# YOTSUBA__Y_Z_ver_1_1b.net
KiCad netlist of a schematic drawn in EAGLE
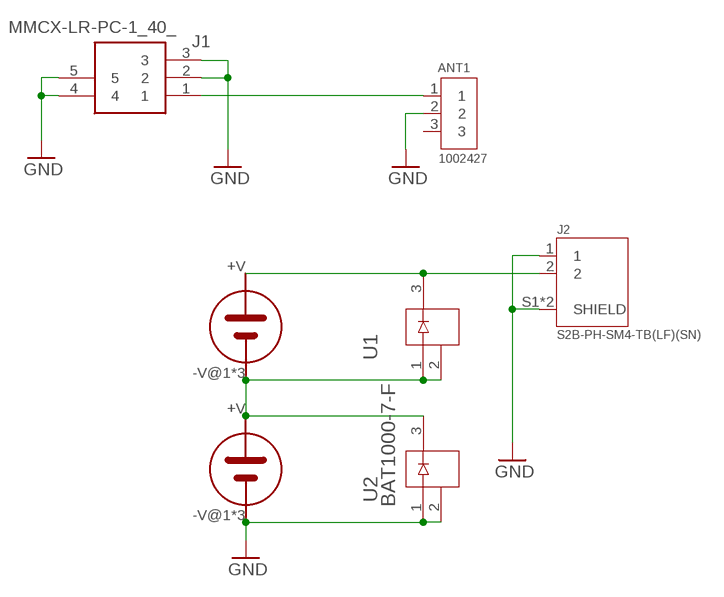
[diagram p0: schematic, sheet 1]

(export (version "E")
  (design (tool "Eeschema 10.0.6"))
  (components
    (comp (ref "ANT1")
      (value "1002427")
      (footprint "eagle-import:ANTENNA_1002427")
      (fields (field (name "DIGI-KEY_PART_NUMBER") "478-1002427TR-ND") (field (name "MF") "Ethertronics/AVX"))
      (libsource (lib "eagle-import") (part "1002427"))
    )
    (comp (ref "J1")
      (value "MMCX-LR-PC-1_40_")
      (footprint "eagle-import:MMCXLRPC140")
      (fields
        (field (name "MANUFACTURER_PART_NUMBER") "MMCX-LR-PC-1(40)")
        (field (name "MOUSER_PART_NUMBER") "798-MMCX-LR-PC-1(40)")
      )
      (libsource (lib "eagle-import") (part "MMCX-LR-PC-1_40_"))
    )
    (comp (ref "J2")
      (value "S2B-PH-SM4-TB(LF)(SN)")
      (footprint "eagle-import:JST_S2B-PH-SM4-TB(LF)(SN)")
      (fields (field (name "DIGI-KEY_PART_NUMBER") "455-1749-2-ND") (field (name "MF") "JST Sales"))
      (libsource (lib "eagle-import") (part "S2B-PH-SM4-TB(LF)(SN)"))
    )
    (comp (ref "U$2")
      (value "3G30A")
      (footprint "eagle-import:SOLAR_3G30A")
      (libsource (lib "eagle-import") (part "3G30A"))
    )
    (comp (ref "U$3")
      (value "3G30A")
      (footprint "eagle-import:SOLAR_3G30A")
      (libsource (lib "eagle-import") (part "3G30A"))
    )
    (comp (ref "U1")
      (value "BAT1000-7-F")
      (footprint "eagle-import:SOT23_BAT_DIO")
      (fields (field (name "COPYRIGHT") "Copyright (C) 2023 Ultra Librarian. All rights reserved."))
      (libsource (lib "eagle-import") (part "BAT1000-7-F"))
    )
    (comp (ref "U2")
      (value "BAT1000-7-F")
      (footprint "eagle-import:SOT23_BAT_DIO")
      (fields (field (name "COPYRIGHT") "Copyright (C) 2023 Ultra Librarian. All rights reserved."))
      (libsource (lib "eagle-import") (part "BAT1000-7-F"))
    )
  )
  (nets
    (net (code "1") (name "GND") (class "Default")
      (node (ref "ANT1") (pin "2") (pinfunction "2_2") (pintype "passive"))
      (node (ref "J1") (pin "2") (pinfunction "2_2") (pintype "bidirectional"))
      (node (ref "J1") (pin "3") (pinfunction "3_3") (pintype "bidirectional"))
      (node (ref "J1") (pin "4") (pinfunction "4_4") (pintype "bidirectional"))
      (node (ref "J1") (pin "5") (pinfunction "5_5") (pintype "bidirectional"))
      (node (ref "J2") (pin "1") (pinfunction "1_1") (pintype "passive"))
      (node (ref "J2") (pin "S1") (pinfunction "SHIELD_S1") (pintype "passive"))
      (node (ref "J2") (pin "S2") (pinfunction "SHIELD_S2") (pintype "passive"))
      (node (ref "U$3") (pin "-V@1") (pinfunction "-V_-V@1") (pintype "bidirectional"))
      (node (ref "U$3") (pin "-V@2") (pinfunction "-V_-V@2") (pintype "bidirectional"))
      (node (ref "U$3") (pin "-V@3") (pinfunction "-V_-V@3") (pintype "bidirectional"))
      (node (ref "U2") (pin "1") (pinfunction "1_1") (pintype "passive"))
      (node (ref "U2") (pin "2") (pinfunction "2_2") (pintype "passive"))
    )
    (net (code "2") (name "Net-(ANT1-Pad1)") (class "Default")
      (node (ref "ANT1") (pin "1") (pinfunction "1_1") (pintype "passive"))
      (node (ref "J1") (pin "1") (pinfunction "1_1") (pintype "bidirectional"))
    )
    (net (code "3") (name "Net-(J2-Pad2)") (class "Default")
      (node (ref "J2") (pin "2") (pinfunction "2_2") (pintype "passive"))
      (node (ref "U$2") (pin "+V") (pinfunction "+V_+V") (pintype "bidirectional"))
      (node (ref "U1") (pin "3") (pinfunction "3_3") (pintype "passive"))
    )
    (net (code "4") (name "Net-(U$2--V-Pad-V@1)") (class "Default")
      (node (ref "U$2") (pin "-V@1") (pinfunction "-V_-V@1") (pintype "bidirectional"))
      (node (ref "U$2") (pin "-V@2") (pinfunction "-V_-V@2") (pintype "bidirectional"))
      (node (ref "U$2") (pin "-V@3") (pinfunction "-V_-V@3") (pintype "bidirectional"))
      (node (ref "U$3") (pin "+V") (pinfunction "+V_+V") (pintype "bidirectional"))
      (node (ref "U1") (pin "1") (pinfunction "1_1") (pintype "passive"))
      (node (ref "U1") (pin "2") (pinfunction "2_2") (pintype "passive"))
      (node (ref "U2") (pin "3") (pinfunction "3_3") (pintype "passive"))
    )
    (net (code "5") (name "unconnected-(ANT1-Pad3)") (class "Default")
      (node (ref "ANT1") (pin "3") (pinfunction "3_3") (pintype "passive"))
    )
  )
)
